# lv_io_current.net
KiCad netlist of a schematic drawn in Altium Designer
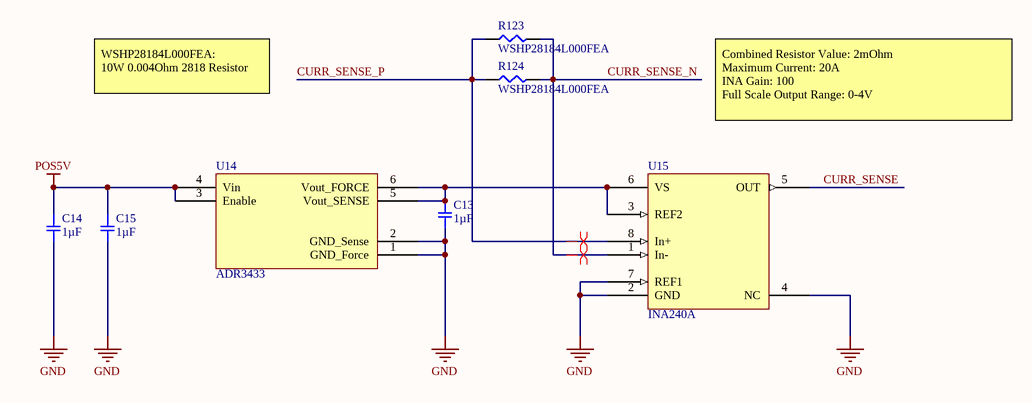
[diagram p0: lv_io_current.SchDoc]

(export (version "E")
  (design (tool "Eeschema 10.0.6"))
  (components
    (comp (ref "C13")
      (value "1µF")
      (footprint "SMD-0805C")
      (description "CAP CER 1UF 25V X7R 0805")
      (fields
        (field (name "PART NUMBER") "GCJ21BR71E105KA12L")
        (field (name "MANUFACTURER") "Murata Electronics North America")
      )
      (libsource (lib "altium-import") (part "root_0_GCJ21BR71E105KA12L_"))
    )
    (comp (ref "C14")
      (value "1µF")
      (footprint "SMD-0805C")
      (description "CAP CER 1UF 25V X7R 0805")
      (fields
        (field (name "PART NUMBER") "GCJ21BR71E105KA12L")
        (field (name "MANUFACTURER") "Murata Electronics North America")
      )
      (libsource (lib "altium-import") (part "root_0_GCJ21BR71E105KA12L_"))
    )
    (comp (ref "C15")
      (value "1µF")
      (footprint "SMD-0805C")
      (description "CAP CER 1UF 25V X7R 0805")
      (fields
        (field (name "PART NUMBER") "GCJ21BR71E105KA12L")
        (field (name "MANUFACTURER") "Murata Electronics North America")
      )
      (libsource (lib "altium-import") (part "root_0_GCJ21BR71E105KA12L_"))
    )
    (comp (ref "R123")
      (value "WSHP28184L000FEA")
      (footprint "RESC7146X15N")
      (description "RES 0.004 OHM 1% 10W 2818")
      (fields (field (name "MANUFACTURER") "Vishay Dale"))
      (libsource (lib "altium-import") (part "root_0_WSHP28184L000FEA_"))
    )
    (comp (ref "R124")
      (value "WSHP28184L000FEA")
      (footprint "RESC7146X15N")
      (description "RES 0.004 OHM 1% 10W 2818")
      (fields (field (name "MANUFACTURER") "Vishay Dale"))
      (libsource (lib "altium-import") (part "root_0_WSHP28184L000FEA_"))
    )
    (comp (ref "U14")
      (value "ADR3433")
      (footprint "SOT95P280X145-6N")
      (description "IC VREF SERIES 3.3V SOT23-6")
      (fields (field (name "MANUFACTURER") "Analog Devices"))
      (libsource (lib "altium-import") (part "root_0_ADR3433_"))
    )
    (comp (ref "U15")
      (value "INA240A")
      (footprint "SOIC127P600X175-8N")
      (description "IC AMP CURRENT SENSE 8-TSSOP")
      (fields (field (name "MANUFACTURER") "TI"))
      (libsource (lib "altium-import") (part "root_0_INA240A_"))
    )
  )
  (nets
    (net (code "1") (name "/CURR_SENSE") (class "Default")
      (node (ref "U15") (pin "5") (pinfunction "OUT_5") (pintype "output"))
    )
    (net (code "2") (name "/CURR_SENSE_N") (class "Default")
      (node (ref "R123") (pin "2") (pinfunction "2_2") (pintype "passive"))
      (node (ref "R124") (pin "2") (pinfunction "2_2") (pintype "passive"))
      (node (ref "U15") (pin "1") (pinfunction "In-_1") (pintype "input"))
    )
    (net (code "3") (name "/CURR_SENSE_P") (class "Default")
      (node (ref "R123") (pin "1") (pinfunction "1_1") (pintype "passive"))
      (node (ref "R124") (pin "1") (pinfunction "1_1") (pintype "passive"))
      (node (ref "U15") (pin "8") (pinfunction "In+_8") (pintype "input"))
    )
    (net (code "4") (name "GND") (class "Default")
      (node (ref "C13") (pin "2") (pinfunction "2_2") (pintype "passive"))
      (node (ref "C14") (pin "2") (pinfunction "2_2") (pintype "passive"))
      (node (ref "C15") (pin "2") (pinfunction "2_2") (pintype "passive"))
      (node (ref "U14") (pin "1") (pinfunction "GND_Force_1") (pintype "power_in"))
      (node (ref "U14") (pin "2") (pinfunction "GND_Sense_2") (pintype "power_in"))
      (node (ref "U15") (pin "2") (pinfunction "GND_2") (pintype "power_in"))
      (node (ref "U15") (pin "4") (pinfunction "NC_4") (pintype "passive"))
      (node (ref "U15") (pin "7") (pinfunction "REF1_7") (pintype "input"))
    )
    (net (code "5") (name "Net-(U14-Vout_FORCE)") (class "Default")
      (node (ref "C13") (pin "1") (pinfunction "1_1") (pintype "passive"))
      (node (ref "U14") (pin "5") (pinfunction "Vout_SENSE_5") (pintype "passive"))
      (node (ref "U14") (pin "6") (pinfunction "Vout_FORCE_6") (pintype "passive"))
      (node (ref "U15") (pin "3") (pinfunction "REF2_3") (pintype "input"))
      (node (ref "U15") (pin "6") (pinfunction "VS_6") (pintype "power_in"))
    )
    (net (code "6") (name "POS5V") (class "Default")
      (node (ref "C14") (pin "1") (pinfunction "1_1") (pintype "passive"))
      (node (ref "C15") (pin "1") (pinfunction "1_1") (pintype "passive"))
      (node (ref "U14") (pin "3") (pinfunction "Enable_3") (pintype "passive"))
      (node (ref "U14") (pin "4") (pinfunction "Vin_4") (pintype "passive"))
    )
  )
)
